# 3Phase_Driver_STUDY.net
KiCad netlist of a schematic drawn in Altium Designer
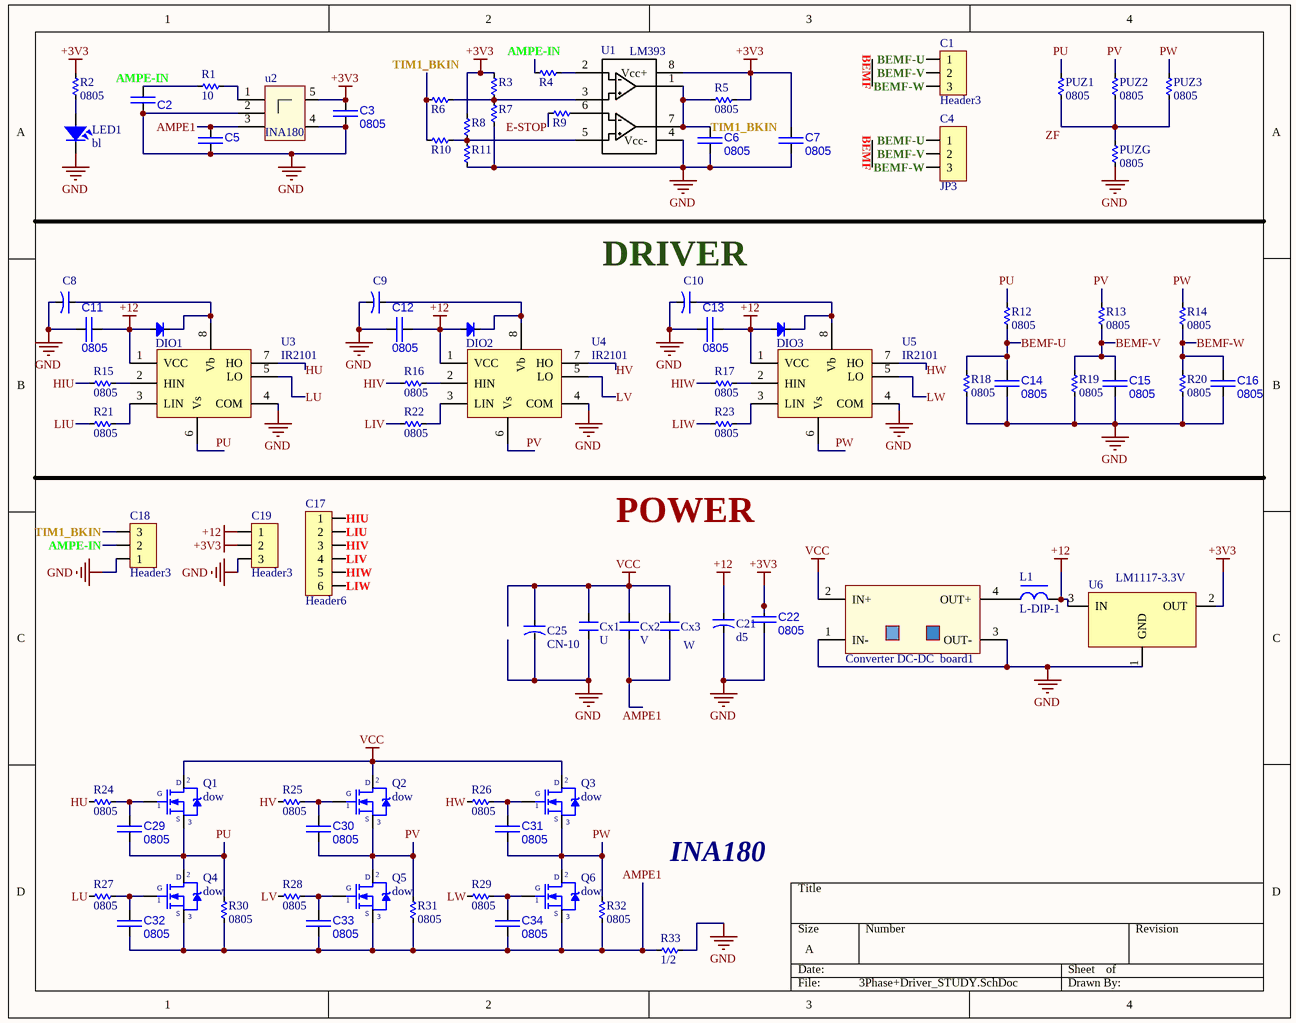
[diagram p0: 3Phase+Driver_STUDY.SchDoc]

(export (version "E")
  (design (tool "Eeschema 10.0.6"))
  (components
    (comp (ref "board1")
      (value "Converter DC-DC")
      (footprint "mini360")
      (description "Step DC-DC")
      (libsource (lib "DT2AM") (part "Converter DC-DC"))
    )
    (comp (ref "C1")
      (value "Header3")
      (footprint "Header3")
      (description "Header IDC, 3 x 1 Pin Vertical 2.54mm Pitch (Non-Boxed, Male)")
      (fields
        (field (name "MANUFACTURER") "Würth Elektronik eiSos GmbH")
        (field (name "PARTNO") "613002143121")
        (field (name "CREATED BY") "Karrer Zheng")
      )
      (libsource (lib "LIBRARY") (part "Header3"))
    )
    (comp (ref "C2")
      (value "approved sub OK")
      (footprint "CAPC2012X135N")
      (description "Capacitor SMD Cer 1.8nF 10% 50V X7R 0805")
      (fields (field (name "TOLERANCE") "±10%"))
      (libsource (lib "My library altium") (part "CAP C_0805"))
    )
    (comp (ref "C3")
      (value "0805")
      (footprint "CAPC2012X135N")
      (description "Capacitor SMD Cer 1.8nF 10% 50V X7R 0805")
      (fields (field (name "TOLERANCE") "±10%") (field (name "Comment") "approved sub OK"))
      (libsource (lib "My library altium") (part "CAP C_0805"))
    )
    (comp (ref "C4")
      (value "JP3")
      (footprint "JP3-C1T")
      (description "WR-PHD 2.54 mm Angled Socket Header")
      (fields
        (field (name "MANUFACTURER") "Würth Elektronik eiSos GmbH")
        (field (name "PARTNO") "613003143121")
        (field (name "CREATED BY") "Karrer Zheng")
      )
      (libsource (lib "LIBRARY") (part "JP3"))
    )
    (comp (ref "C5")
      (value "approved sub OK")
      (footprint "CAPC2012X135N")
      (description "Capacitor SMD Cer 1.8nF 10% 50V X7R 0805")
      (fields (field (name "TOLERANCE") "±10%"))
      (libsource (lib "My library altium") (part "CAP C_0805"))
    )
    (comp (ref "C6")
      (value "0805")
      (footprint "CAPC2012X135N")
      (description "Capacitor SMD Cer 1.8nF 10% 50V X7R 0805")
      (fields (field (name "TOLERANCE") "±10%") (field (name "Comment") "approved sub OK"))
      (libsource (lib "My library altium") (part "CAP C_0805"))
    )
    (comp (ref "C7")
      (value "0805")
      (footprint "CAPC2012X135N")
      (description "Capacitor SMD Cer 1.8nF 10% 50V X7R 0805")
      (fields (field (name "TOLERANCE") "±10%") (field (name "Comment") "approved sub OK"))
      (libsource (lib "My library altium") (part "CAP C_0805"))
    )
    (comp (ref "C8")
      (value "CN-ALU-SMD")
      (footprint "CAP-ALU-SMD-5.5x5.5")
      (description "Polarized Capacitor (Axial)")
      (fields (field (name "PUBLISHER") "Altium Limited"))
      (libsource (lib "LIBRARY") (part "CN-ALU-SMD"))
    )
    (comp (ref "C9")
      (value "CN-ALU-SMD")
      (footprint "CAP-ALU-SMD-5.5x5.5")
      (description "Polarized Capacitor (Axial)")
      (fields (field (name "PUBLISHER") "Altium Limited"))
      (libsource (lib "LIBRARY") (part "CN-ALU-SMD"))
    )
    (comp (ref "C10")
      (value "CN-ALU-SMD")
      (footprint "CAP-ALU-SMD-5.5x5.5")
      (description "Polarized Capacitor (Axial)")
      (fields (field (name "PUBLISHER") "Altium Limited"))
      (libsource (lib "LIBRARY") (part "CN-ALU-SMD"))
    )
    (comp (ref "C11")
      (value "0805")
      (footprint "CAPC2012X135N")
      (description "Capacitor SMD Cer 1.8nF 10% 50V X7R 0805")
      (fields (field (name "TOLERANCE") "±10%") (field (name "Comment") "approved sub OK"))
      (libsource (lib "My library altium") (part "CAP C_0805"))
    )
    (comp (ref "C12")
      (value "0805")
      (footprint "CAPC2012X135N")
      (description "Capacitor SMD Cer 1.8nF 10% 50V X7R 0805")
      (fields (field (name "TOLERANCE") "±10%") (field (name "Comment") "approved sub OK"))
      (libsource (lib "My library altium") (part "CAP C_0805"))
    )
    (comp (ref "C13")
      (value "0805")
      (footprint "CAPC2012X135N")
      (description "Capacitor SMD Cer 1.8nF 10% 50V X7R 0805")
      (fields (field (name "TOLERANCE") "±10%") (field (name "Comment") "approved sub OK"))
      (libsource (lib "My library altium") (part "CAP C_0805"))
    )
    (comp (ref "C14")
      (value "0805")
      (footprint "CAPC2012X135N")
      (description "Capacitor SMD Cer 1.8nF 10% 50V X7R 0805")
      (fields (field (name "TOLERANCE") "±10%") (field (name "Comment") "approved sub OK"))
      (libsource (lib "My library altium") (part "CAP C_0805"))
    )
    (comp (ref "C15")
      (value "0805")
      (footprint "CAPC2012X135N")
      (description "Capacitor SMD Cer 1.8nF 10% 50V X7R 0805")
      (fields (field (name "TOLERANCE") "±10%") (field (name "Comment") "approved sub OK"))
      (libsource (lib "My library altium") (part "CAP C_0805"))
    )
    (comp (ref "C16")
      (value "0805")
      (footprint "CAPC2012X135N")
      (description "Capacitor SMD Cer 1.8nF 10% 50V X7R 0805")
      (fields (field (name "TOLERANCE") "±10%") (field (name "Comment") "approved sub OK"))
      (libsource (lib "My library altium") (part "CAP C_0805"))
    )
    (comp (ref "C17")
      (value "Header6")
      (footprint "Header6")
      (description "Header IDC, 6 x 1 Pin Vertical 2.54mm Pitch (Non-Boxed, Male)")
      (fields
        (field (name "MANUFACTURER") "Würth Elektronik eiSos GmbH")
        (field (name "PARTNO") "613002143121")
        (field (name "CREATED BY") "Karrer Zheng")
      )
      (libsource (lib "LIBRARY") (part "Header6"))
    )
    (comp (ref "C18")
      (value "Header3")
      (footprint "Header3")
      (description "Header IDC, 3 x 1 Pin Vertical 2.54mm Pitch (Non-Boxed, Male)")
      (fields
        (field (name "MANUFACTURER") "Würth Elektronik eiSos GmbH")
        (field (name "PARTNO") "613002143121")
        (field (name "CREATED BY") "Karrer Zheng")
      )
      (libsource (lib "") (part "Header3_1"))
    )
    (comp (ref "C19")
      (value "Header3")
      (footprint "Header3")
      (description "Header IDC, 3 x 1 Pin Vertical 2.54mm Pitch (Non-Boxed, Male)")
      (fields
        (field (name "MANUFACTURER") "Würth Elektronik eiSos GmbH")
        (field (name "PARTNO") "613002143121")
        (field (name "CREATED BY") "Karrer Zheng")
      )
      (libsource (lib "LIBRARY") (part "Header3"))
    )
    (comp (ref "C21")
      (value "d5")
      (footprint "CA-ALU-5")
      (description "Capacitor (Semiconductor SIM Model)")
      (fields (field (name "PUBLISHER") "Altium Limited"))
      (libsource (lib "LIBRARY") (part "CN-ALU-DIP"))
    )
    (comp (ref "C22")
      (value "0805")
      (footprint "CAPC2012X135N")
      (description "Capacitor SMD Cer 1.8nF 10% 50V X7R 0805")
      (fields (field (name "TOLERANCE") "±10%") (field (name "Comment") "approved sub OK"))
      (libsource (lib "My library altium") (part "CAP C_0805"))
    )
    (comp (ref "C25")
      (value "CN-10")
      (footprint "CA-ALU-10")
      (description "Capacitor (Semiconductor SIM Model)")
      (fields (field (name "PUBLISHER") "Altium Limited"))
      (libsource (lib "LIBRARY") (part "CN-ALU-DIP"))
    )
    (comp (ref "C29")
      (value "0805")
      (footprint "CAPC2012X135N")
      (description "Capacitor SMD Cer 1.8nF 10% 50V X7R 0805")
      (fields (field (name "TOLERANCE") "±10%") (field (name "Comment") "approved sub OK"))
      (libsource (lib "My library altium") (part "CAP C_0805"))
    )
    (comp (ref "C30")
      (value "0805")
      (footprint "CAPC2012X135N")
      (description "Capacitor SMD Cer 1.8nF 10% 50V X7R 0805")
      (fields (field (name "TOLERANCE") "±10%") (field (name "Comment") "approved sub OK"))
      (libsource (lib "My library altium") (part "CAP C_0805"))
    )
    (comp (ref "C31")
      (value "0805")
      (footprint "CAPC2012X135N")
      (description "Capacitor SMD Cer 1.8nF 10% 50V X7R 0805")
      (fields (field (name "TOLERANCE") "±10%") (field (name "Comment") "approved sub OK"))
      (libsource (lib "My library altium") (part "CAP C_0805"))
    )
    (comp (ref "C32")
      (value "0805")
      (footprint "CAPC2012X135N")
      (description "Capacitor SMD Cer 1.8nF 10% 50V X7R 0805")
      (fields (field (name "TOLERANCE") "±10%") (field (name "Comment") "approved sub OK"))
      (libsource (lib "My library altium") (part "CAP C_0805"))
    )
    (comp (ref "C33")
      (value "0805")
      (footprint "CAPC2012X135N")
      (description "Capacitor SMD Cer 1.8nF 10% 50V X7R 0805")
      (fields (field (name "TOLERANCE") "±10%") (field (name "Comment") "approved sub OK"))
      (libsource (lib "My library altium") (part "CAP C_0805"))
    )
    (comp (ref "C34")
      (value "0805")
      (footprint "CAPC2012X135N")
      (description "Capacitor SMD Cer 1.8nF 10% 50V X7R 0805")
      (fields (field (name "TOLERANCE") "±10%") (field (name "Comment") "approved sub OK"))
      (libsource (lib "My library altium") (part "CAP C_0805"))
    )
    (comp (ref "Cx1") (value "U") (footprint "CN2-LT") (libsource (lib "LIBRARY") (part "CN")))
    (comp (ref "Cx2") (value "V") (footprint "CN2-LT") (libsource (lib "LIBRARY") (part "CN")))
    (comp (ref "Cx3") (value "W") (footprint "CN2-LT") (libsource (lib "LIBRARY") (part "CN")))
    (comp (ref "DIO1")
      (value "Diode SMD")
      (footprint "DIO-SMD-123")
      (description "Default Diode")
      (fields (field (name "PUBLISHER") "Altium Limited"))
      (libsource (lib "LIBRARY") (part "Diode SMD"))
    )
    (comp (ref "DIO2")
      (value "Diode SMD")
      (footprint "DIO-SMD-123")
      (description "Default Diode")
      (fields (field (name "PUBLISHER") "Altium Limited"))
      (libsource (lib "LIBRARY") (part "Diode SMD"))
    )
    (comp (ref "DIO3")
      (value "Diode SMD")
      (footprint "DIO-SMD-123")
      (description "Default Diode")
      (fields (field (name "PUBLISHER") "Altium Limited"))
      (libsource (lib "LIBRARY") (part "Diode SMD"))
    )
    (comp (ref "L1")
      (value "L-DIP-1")
      (footprint "L-DIP-M-5.3")
      (description "Inductor")
      (libsource (lib "LIBRARY") (part "L-DIP-1"))
    )
    (comp (ref "LED1") (value "bl") (footprint "LED-0805-Blue") (libsource (lib "LIBRARY") (part "LED SMD")))
    (comp (ref "PUZ1")
      (value "0805")
      (footprint "RES-SMD-0805")
      (description "Resistor")
      (fields
        (field (name "MANUFACTURER") "Generic Components")
        (field (name "PUBLISHER") "Altium Hobart Technology Centre")
      )
      (libsource (lib "LIBRARY") (part "Res-SMD"))
    )
    (comp (ref "PUZ2")
      (value "0805")
      (footprint "RES-SMD-0805")
      (description "Resistor")
      (fields
        (field (name "MANUFACTURER") "Generic Components")
        (field (name "PUBLISHER") "Altium Hobart Technology Centre")
      )
      (libsource (lib "LIBRARY") (part "Res-SMD"))
    )
    (comp (ref "PUZ3")
      (value "0805")
      (footprint "RES-SMD-0805")
      (description "Resistor")
      (fields
        (field (name "MANUFACTURER") "Generic Components")
        (field (name "PUBLISHER") "Altium Hobart Technology Centre")
      )
      (libsource (lib "LIBRARY") (part "Res-SMD"))
    )
    (comp (ref "PUZG")
      (value "0805")
      (footprint "RES-SMD-0805")
      (description "Resistor")
      (fields
        (field (name "MANUFACTURER") "Generic Components")
        (field (name "PUBLISHER") "Altium Hobart Technology Centre")
      )
      (libsource (lib "LIBRARY") (part "Res-SMD"))
    )
    (comp (ref "Q1")
      (value "dow")
      (footprint "TO220NH")
      (description "MOSFET N - CHANNEL 500V - 0.75 - 8A - TO-220")
      (libsource (lib "LIBRARY") (part "IRF840"))
    )
    (comp (ref "Q2")
      (value "dow")
      (footprint "TO220NH")
      (description "MOSFET N - CHANNEL 500V - 0.75 - 8A - TO-220")
      (libsource (lib "LIBRARY") (part "IRF840"))
    )
    (comp (ref "Q3")
      (value "dow")
      (footprint "TO220NH")
      (description "MOSFET N - CHANNEL 500V - 0.75 - 8A - TO-220")
      (libsource (lib "LIBRARY") (part "IRF840"))
    )
    (comp (ref "Q4")
      (value "dow")
      (footprint "TO220NH")
      (description "MOSFET N - CHANNEL 500V - 0.75 - 8A - TO-220")
      (libsource (lib "LIBRARY") (part "IRF840"))
    )
    (comp (ref "Q5")
      (value "dow")
      (footprint "TO220NH")
      (description "MOSFET N - CHANNEL 500V - 0.75 - 8A - TO-220")
      (libsource (lib "LIBRARY") (part "IRF840"))
    )
    (comp (ref "Q6")
      (value "dow")
      (footprint "TO220NH")
      (description "MOSFET N - CHANNEL 500V - 0.75 - 8A - TO-220")
      (libsource (lib "LIBRARY") (part "IRF840"))
    )
    (comp (ref "R1")
      (value "10")
      (footprint "RES-SMD-0805")
      (description "Resistor")
      (fields
        (field (name "MANUFACTURER") "Generic Components")
        (field (name "PUBLISHER") "Altium Hobart Technology Centre")
      )
      (libsource (lib "LIBRARY") (part "Res-SMD"))
    )
    (comp (ref "R2")
      (value "0805")
      (footprint "RES-SMD-0805")
      (description "Resistor")
      (fields
        (field (name "MANUFACTURER") "Generic Components")
        (field (name "PUBLISHER") "Altium Hobart Technology Centre")
      )
      (libsource (lib "LIBRARY") (part "Res-SMD"))
    )
    (comp (ref "R3")
      (value "0805")
      (footprint "RES-SMD-0805")
      (description "Resistor")
      (fields
        (field (name "MANUFACTURER") "Generic Components")
        (field (name "PUBLISHER") "Altium Hobart Technology Centre")
      )
      (libsource (lib "LIBRARY") (part "Res-SMD"))
    )
    (comp (ref "R4")
      (value "0805")
      (footprint "RES-SMD-0805")
      (description "Resistor")
      (fields
        (field (name "MANUFACTURER") "Generic Components")
        (field (name "PUBLISHER") "Altium Hobart Technology Centre")
      )
      (libsource (lib "LIBRARY") (part "Res-SMD"))
    )
    (comp (ref "R5")
      (value "0805")
      (footprint "RES-SMD-0805")
      (description "Resistor")
      (fields
        (field (name "MANUFACTURER") "Generic Components")
        (field (name "PUBLISHER") "Altium Hobart Technology Centre")
      )
      (libsource (lib "LIBRARY") (part "Res-SMD"))
    )
    (comp (ref "R6")
      (value "0805")
      (footprint "RES-SMD-0805")
      (description "Resistor")
      (fields
        (field (name "MANUFACTURER") "Generic Components")
        (field (name "PUBLISHER") "Altium Hobart Technology Centre")
      )
      (libsource (lib "LIBRARY") (part "Res-SMD"))
    )
    (comp (ref "R7")
      (value "0805")
      (footprint "RES-SMD-0805")
      (description "Resistor")
      (fields
        (field (name "MANUFACTURER") "Generic Components")
        (field (name "PUBLISHER") "Altium Hobart Technology Centre")
      )
      (libsource (lib "LIBRARY") (part "Res-SMD"))
    )
    (comp (ref "R8")
      (value "0805")
      (footprint "RES-SMD-0805")
      (description "Resistor")
      (fields
        (field (name "MANUFACTURER") "Generic Components")
        (field (name "PUBLISHER") "Altium Hobart Technology Centre")
      )
      (libsource (lib "LIBRARY") (part "Res-SMD"))
    )
    (comp (ref "R9")
      (value "0805")
      (footprint "RES-SMD-0805")
      (description "Resistor")
      (fields
        (field (name "MANUFACTURER") "Generic Components")
        (field (name "PUBLISHER") "Altium Hobart Technology Centre")
      )
      (libsource (lib "LIBRARY") (part "Res-SMD"))
    )
    (comp (ref "R10")
      (value "0805")
      (footprint "RES-SMD-0805")
      (description "Resistor")
      (fields
        (field (name "MANUFACTURER") "Generic Components")
        (field (name "PUBLISHER") "Altium Hobart Technology Centre")
      )
      (libsource (lib "LIBRARY") (part "Res-SMD"))
    )
    (comp (ref "R11")
      (value "0805")
      (footprint "RES-SMD-0805")
      (description "Resistor")
      (fields
        (field (name "MANUFACTURER") "Generic Components")
        (field (name "PUBLISHER") "Altium Hobart Technology Centre")
      )
      (libsource (lib "LIBRARY") (part "Res-SMD"))
    )
    (comp (ref "R12")
      (value "0805")
      (footprint "RES-SMD-0805")
      (description "Resistor")
      (fields
        (field (name "MANUFACTURER") "Generic Components")
        (field (name "PUBLISHER") "Altium Hobart Technology Centre")
      )
      (libsource (lib "LIBRARY") (part "Res-SMD"))
    )
    (comp (ref "R13")
      (value "0805")
      (footprint "RES-SMD-0805")
      (description "Resistor")
      (fields
        (field (name "MANUFACTURER") "Generic Components")
        (field (name "PUBLISHER") "Altium Hobart Technology Centre")
      )
      (libsource (lib "LIBRARY") (part "Res-SMD"))
    )
    (comp (ref "R14")
      (value "0805")
      (footprint "RES-SMD-0805")
      (description "Resistor")
      (fields
        (field (name "MANUFACTURER") "Generic Components")
        (field (name "PUBLISHER") "Altium Hobart Technology Centre")
      )
      (libsource (lib "LIBRARY") (part "Res-SMD"))
    )
    (comp (ref "R15")
      (value "0805")
      (footprint "RES-SMD-0805")
      (description "Resistor")
      (fields
        (field (name "MANUFACTURER") "Generic Components")
        (field (name "PUBLISHER") "Altium Hobart Technology Centre")
      )
      (libsource (lib "LIBRARY") (part "Res-SMD"))
    )
    (comp (ref "R16")
      (value "0805")
      (footprint "RES-SMD-0805")
      (description "Resistor")
      (fields
        (field (name "MANUFACTURER") "Generic Components")
        (field (name "PUBLISHER") "Altium Hobart Technology Centre")
      )
      (libsource (lib "LIBRARY") (part "Res-SMD"))
    )
    (comp (ref "R17")
      (value "0805")
      (footprint "RES-SMD-0805")
      (description "Resistor")
      (fields
        (field (name "MANUFACTURER") "Generic Components")
        (field (name "PUBLISHER") "Altium Hobart Technology Centre")
      )
      (libsource (lib "LIBRARY") (part "Res-SMD"))
    )
    (comp (ref "R18")
      (value "0805")
      (footprint "RES-SMD-0805")
      (description "Resistor")
      (fields
        (field (name "MANUFACTURER") "Generic Components")
        (field (name "PUBLISHER") "Altium Hobart Technology Centre")
      )
      (libsource (lib "LIBRARY") (part "Res-SMD"))
    )
    (comp (ref "R19")
      (value "0805")
      (footprint "RES-SMD-0805")
      (description "Resistor")
      (fields
        (field (name "MANUFACTURER") "Generic Components")
        (field (name "PUBLISHER") "Altium Hobart Technology Centre")
      )
      (libsource (lib "LIBRARY") (part "Res-SMD"))
    )
    (comp (ref "R20")
      (value "0805")
      (footprint "RES-SMD-0805")
      (description "Resistor")
      (fields
        (field (name "MANUFACTURER") "Generic Components")
        (field (name "PUBLISHER") "Altium Hobart Technology Centre")
      )
      (libsource (lib "LIBRARY") (part "Res-SMD"))
    )
    (comp (ref "R21")
      (value "0805")
      (footprint "RES-SMD-0805")
      (description "Resistor")
      (fields
        (field (name "MANUFACTURER") "Generic Components")
        (field (name "PUBLISHER") "Altium Hobart Technology Centre")
      )
      (libsource (lib "LIBRARY") (part "Res-SMD"))
    )
    (comp (ref "R22")
      (value "0805")
      (footprint "RES-SMD-0805")
      (description "Resistor")
      (fields
        (field (name "MANUFACTURER") "Generic Components")
        (field (name "PUBLISHER") "Altium Hobart Technology Centre")
      )
      (libsource (lib "LIBRARY") (part "Res-SMD"))
    )
    (comp (ref "R23")
      (value "0805")
      (footprint "RES-SMD-0805")
      (description "Resistor")
      (fields
        (field (name "MANUFACTURER") "Generic Components")
        (field (name "PUBLISHER") "Altium Hobart Technology Centre")
      )
      (libsource (lib "LIBRARY") (part "Res-SMD"))
    )
    (comp (ref "R24")
      (value "0805")
      (footprint "RES-SMD-0805")
      (description "Resistor")
      (fields
        (field (name "MANUFACTURER") "Generic Components")
        (field (name "PUBLISHER") "Altium Hobart Technology Centre")
      )
      (libsource (lib "LIBRARY") (part "Res-SMD"))
    )
    (comp (ref "R25")
      (value "0805")
      (footprint "RES-SMD-0805")
      (description "Resistor")
      (fields
        (field (name "MANUFACTURER") "Generic Components")
        (field (name "PUBLISHER") "Altium Hobart Technology Centre")
      )
      (libsource (lib "LIBRARY") (part "Res-SMD"))
    )
    (comp (ref "R26")
      (value "0805")
      (footprint "RES-SMD-0805")
      (description "Resistor")
      (fields
        (field (name "MANUFACTURER") "Generic Components")
        (field (name "PUBLISHER") "Altium Hobart Technology Centre")
      )
      (libsource (lib "LIBRARY") (part "Res-SMD"))
    )
    (comp (ref "R27")
      (value "0805")
      (footprint "RES-SMD-0805")
      (description "Resistor")
      (fields
        (field (name "MANUFACTURER") "Generic Components")
        (field (name "PUBLISHER") "Altium Hobart Technology Centre")
      )
      (libsource (lib "LIBRARY") (part "Res-SMD"))
    )
    (comp (ref "R28")
      (value "0805")
      (footprint "RES-SMD-0805")
      (description "Resistor")
      (fields
        (field (name "MANUFACTURER") "Generic Components")
        (field (name "PUBLISHER") "Altium Hobart Technology Centre")
      )
      (libsource (lib "LIBRARY") (part "Res-SMD"))
    )
    (comp (ref "R29")
      (value "0805")
      (footprint "RES-SMD-0805")
      (description "Resistor")
      (fields
        (field (name "MANUFACTURER") "Generic Components")
        (field (name "PUBLISHER") "Altium Hobart Technology Centre")
      )
      (libsource (lib "LIBRARY") (part "Res-SMD"))
    )
    (comp (ref "R30")
      (value "0805")
      (footprint "RES-SMD-0805")
      (description "Resistor")
      (fields
        (field (name "MANUFACTURER") "Generic Components")
        (field (name "PUBLISHER") "Altium Hobart Technology Centre")
      )
      (libsource (lib "LIBRARY") (part "Res-SMD"))
    )
    (comp (ref "R31")
      (value "0805")
      (footprint "RES-SMD-0805")
      (description "Resistor")
      (fields
        (field (name "MANUFACTURER") "Generic Components")
        (field (name "PUBLISHER") "Altium Hobart Technology Centre")
      )
      (libsource (lib "LIBRARY") (part "Res-SMD"))
    )
    (comp (ref "R32")
      (value "0805")
      (footprint "RES-SMD-0805")
      (description "Resistor")
      (fields
        (field (name "MANUFACTURER") "Generic Components")
        (field (name "PUBLISHER") "Altium Hobart Technology Centre")
      )
      (libsource (lib "LIBRARY") (part "Res-SMD"))
    )
    (comp (ref "R33")
      (value "1/2")
      (footprint "RES-1/2W")
      (description "Res")
      (fields
        (field (name "MANUFACTURER") "Generic Components")
        (field (name "PUBLISHER") "Altium Hobart Technology Centre")
      )
      (libsource (lib "LIBRARY") (part "Res"))
    )
    (comp (ref "U1")
      (value "LM393")
      (footprint "SO8")
      (description "IC DUAL COMPARATOR")
      (libsource (lib "LIBRARY") (part "LM393"))
    )
    (comp (ref "u2")
      (value "INA180")
      (footprint "SOT-23-5")
      (description "SMD_IC_SOT-23-5")
      (libsource (lib "DT2AM") (part "SOT-23-5_SMD"))
    )
    (comp (ref "U3")
      (value "IR2101")
      (footprint "SO8")
      (description "Half-Bridge Driver")
      (libsource (lib "LIBRARY") (part "IR2101S"))
    )
    (comp (ref "U4")
      (value "IR2101")
      (footprint "SO8")
      (description "Half-Bridge Driver")
      (libsource (lib "LIBRARY") (part "IR2101S"))
    )
    (comp (ref "U5")
      (value "IR2101")
      (footprint "SO8")
      (description "Half-Bridge Driver")
      (libsource (lib "LIBRARY") (part "IR2101S"))
    )
    (comp (ref "U6")
      (value "LM1117-3.3V")
      (footprint "SOT223")
      (description "800mA Low-Dropout Linear Regulator")
      (fields (field (name "CREATOR") "Nguyen Ba Bien"))
      (libsource (lib "LIBRARY") (part "LM1117"))
    )
  )
  (nets
    (net (code "1") (name "+3V3") (class "Default")
      (node (ref "C19") (pin "2") (pinfunction "2_2") (pintype "passive"))
      (node (ref "C22") (pin "2") (pintype "passive"))
      (node (ref "C3") (pin "2") (pintype "passive"))
      (node (ref "C7") (pin "2") (pintype "passive"))
      (node (ref "R2") (pin "1") (pinfunction "1_1") (pintype "passive"))
      (node (ref "R3") (pin "2") (pinfunction "2_2") (pintype "passive"))
      (node (ref "R5") (pin "2") (pinfunction "2_2") (pintype "passive"))
      (node (ref "R8") (pin "2") (pinfunction "2_2") (pintype "passive"))
      (node (ref "U1") (pin "8") (pinfunction "Vcc+_8") (pintype "passive"))
      (node (ref "U6") (pin "2") (pinfunction "OUT_2") (pintype "passive"))
      (node (ref "u2") (pin "5") (pinfunction "OUT_5") (pintype "passive"))
    )
    (net (code "2") (name "+12") (class "Default")
      (node (ref "C11") (pin "2") (pintype "passive"))
      (node (ref "C12") (pin "2") (pintype "passive"))
      (node (ref "C13") (pin "2") (pintype "passive"))
      (node (ref "C19") (pin "1") (pinfunction "1_1") (pintype "passive"))
      (node (ref "C21") (pin "1") (pinfunction "1_1") (pintype "passive"))
      (node (ref "DIO1") (pin "1") (pinfunction "A_1") (pintype "passive"))
      (node (ref "DIO2") (pin "1") (pinfunction "A_1") (pintype "passive"))
      (node (ref "DIO3") (pin "1") (pinfunction "A_1") (pintype "passive"))
      (node (ref "L1") (pin "2") (pinfunction "2_2") (pintype "passive"))
      (node (ref "U3") (pin "1") (pinfunction "VCC_1") (pintype "passive"))
      (node (ref "U4") (pin "1") (pinfunction "VCC_1") (pintype "passive"))
      (node (ref "U5") (pin "1") (pinfunction "VCC_1") (pintype "passive"))
      (node (ref "U6") (pin "3") (pinfunction "IN_3") (pintype "passive"))
    )
    (net (code "3") (name "/AMPE-IN") (class "Default")
      (node (ref "C18") (pin "2") (pinfunction "2_2") (pintype "passive"))
      (node (ref "C2") (pin "1") (pintype "passive"))
      (node (ref "R1") (pin "2") (pinfunction "2_2") (pintype "passive"))
      (node (ref "R4") (pin "2") (pinfunction "2_2") (pintype "passive"))
    )
    (net (code "4") (name "/AMPE1") (class "Default")
      (node (ref "C32") (pin "2") (pintype "passive"))
      (node (ref "C33") (pin "2") (pintype "passive"))
      (node (ref "C34") (pin "2") (pintype "passive"))
      (node (ref "C5") (pin "2") (pintype "passive"))
      (node (ref "Cx2") (pin "1") (pinfunction "1_1") (pintype "passive"))
      (node (ref "Cx3") (pin "1") (pinfunction "1_1") (pintype "passive"))
      (node (ref "Q4") (pin "3") (pinfunction "S_3") (pintype "passive"))
      (node (ref "Q5") (pin "3") (pinfunction "S_3") (pintype "passive"))
      (node (ref "Q6") (pin "3") (pinfunction "S_3") (pintype "passive"))
      (node (ref "R30") (pin "2") (pinfunction "2_2") (pintype "passive"))
      (node (ref "R31") (pin "2") (pinfunction "2_2") (pintype "passive"))
      (node (ref "R32") (pin "2") (pinfunction "2_2") (pintype "passive"))
      (node (ref "R33") (pin "2") (pinfunction "2_2") (pintype "passive"))
      (node (ref "u2") (pin "3") (pinfunction "OUT_3") (pintype "passive"))
    )
    (net (code "5") (name "/BEMF-U") (class "Default")
      (node (ref "C1") (pin "1") (pinfunction "1_1") (pintype "passive"))
      (node (ref "C14") (pin "1") (pintype "passive"))
      (node (ref "C4") (pin "1") (pinfunction "1_1") (pintype "passive"))
      (node (ref "R12") (pin "2") (pinfunction "2_2") (pintype "passive"))
      (node (ref "R18") (pin "1") (pinfunction "1_1") (pintype "passive"))
    )
    (net (code "6") (name "/BEMF-V") (class "Default")
      (node (ref "C1") (pin "2") (pinfunction "2_2") (pintype "passive"))
      (node (ref "C15") (pin "1") (pintype "passive"))
      (node (ref "C4") (pin "2") (pinfunction "2_2") (pintype "passive"))
      (node (ref "R13") (pin "2") (pinfunction "2_2") (pintype "passive"))
      (node (ref "R19") (pin "1") (pinfunction "1_1") (pintype "passive"))
    )
    (net (code "7") (name "/BEMF-W") (class "Default")
      (node (ref "C1") (pin "3") (pinfunction "3_3") (pintype "passive"))
      (node (ref "C16") (pin "1") (pintype "passive"))
      (node (ref "C4") (pin "3") (pinfunction "3_3") (pintype "passive"))
      (node (ref "R14") (pin "2") (pinfunction "2_2") (pintype "passive"))
      (node (ref "R20") (pin "1") (pinfunction "1_1") (pintype "passive"))
    )
    (net (code "8") (name "/E-STOP") (class "Default")
      (node (ref "R9") (pin "2") (pinfunction "2_2") (pintype "passive"))
    )
    (net (code "9") (name "/HIU") (class "Default")
      (node (ref "C17") (pin "1") (pinfunction "1_1") (pintype "passive"))
      (node (ref "R15") (pin "2") (pinfunction "2_2") (pintype "passive"))
    )
    (net (code "10") (name "/HIV") (class "Default")
      (node (ref "C17") (pin "3") (pinfunction "3_3") (pintype "passive"))
      (node (ref "R16") (pin "2") (pinfunction "2_2") (pintype "passive"))
    )
    (net (code "11") (name "/HIW") (class "Default")
      (node (ref "C17") (pin "5") (pinfunction "5_5") (pintype "passive"))
      (node (ref "R17") (pin "2") (pinfunction "2_2") (pintype "passive"))
    )
    (net (code "12") (name "/HU") (class "Default")
      (node (ref "R24") (pin "2") (pinfunction "2_2") (pintype "passive"))
      (node (ref "U3") (pin "7") (pinfunction "HO_7") (pintype "passive"))
    )
    (net (code "13") (name "/HV") (class "Default")
      (node (ref "R25") (pin "2") (pinfunction "2_2") (pintype "passive"))
      (node (ref "U4") (pin "7") (pinfunction "HO_7") (pintype "passive"))
    )
    (net (code "14") (name "/HW") (class "Default")
      (node (ref "R26") (pin "2") (pinfunction "2_2") (pintype "passive"))
      (node (ref "U5") (pin "7") (pinfunction "HO_7") (pintype "passive"))
    )
    (net (code "15") (name "/LIU") (class "Default")
      (node (ref "C17") (pin "2") (pinfunction "2_2") (pintype "passive"))
      (node (ref "R21") (pin "2") (pinfunction "2_2") (pintype "passive"))
    )
    (net (code "16") (name "/LIV") (class "Default")
      (node (ref "C17") (pin "4") (pinfunction "4_4") (pintype "passive"))
      (node (ref "R22") (pin "2") (pinfunction "2_2") (pintype "passive"))
    )
    (net (code "17") (name "/LIW") (class "Default")
      (node (ref "C17") (pin "6") (pinfunction "6_6") (pintype "passive"))
      (node (ref "R23") (pin "2") (pinfunction "2_2") (pintype "passive"))
    )
    (net (code "18") (name "/LU") (class "Default")
      (node (ref "R27") (pin "2") (pinfunction "2_2") (pintype "passive"))
      (node (ref "U3") (pin "5") (pinfunction "LO_5") (pintype "passive"))
    )
    (net (code "19") (name "/LV") (class "Default")
      (node (ref "R28") (pin "2") (pinfunction "2_2") (pintype "passive"))
      (node (ref "U4") (pin "5") (pinfunction "LO_5") (pintype "passive"))
    )
    (net (code "20") (name "/LW") (class "Default")
      (node (ref "R29") (pin "2") (pinfunction "2_2") (pintype "passive"))
      (node (ref "U5") (pin "5") (pinfunction "LO_5") (pintype "passive"))
    )
    (net (code "21") (name "/PU") (class "Default")
      (node (ref "C29") (pin "2") (pintype "passive"))
      (node (ref "PUZ1") (pin "1") (pinfunction "1_1") (pintype "passive"))
      (node (ref "Q1") (pin "3") (pinfunction "S_3") (pintype "passive"))
      (node (ref "Q4") (pin "2") (pinfunction "D_2") (pintype "passive"))
      (node (ref "R12") (pin "1") (pinfunction "1_1") (pintype "passive"))
      (node (ref "R30") (pin "1") (pinfunction "1_1") (pintype "passive"))
      (node (ref "U3") (pin "6") (pinfunction "Vs_6") (pintype "passive"))
    )
    (net (code "22") (name "/PV") (class "Default")
      (node (ref "C30") (pin "2") (pintype "passive"))
      (node (ref "PUZ2") (pin "1") (pinfunction "1_1") (pintype "passive"))
      (node (ref "Q2") (pin "3") (pinfunction "S_3") (pintype "passive"))
      (node (ref "Q5") (pin "2") (pinfunction "D_2") (pintype "passive"))
      (node (ref "R13") (pin "1") (pinfunction "1_1") (pintype "passive"))
      (node (ref "R31") (pin "1") (pinfunction "1_1") (pintype "passive"))
      (node (ref "U4") (pin "6") (pinfunction "Vs_6") (pintype "passive"))
    )
    (net (code "23") (name "/PW") (class "Default")
      (node (ref "C31") (pin "2") (pintype "passive"))
      (node (ref "PUZ3") (pin "1") (pinfunction "1_1") (pintype "passive"))
      (node (ref "Q3") (pin "3") (pinfunction "S_3") (pintype "passive"))
      (node (ref "Q6") (pin "2") (pinfunction "D_2") (pintype "passive"))
      (node (ref "R14") (pin "1") (pinfunction "1_1") (pintype "passive"))
      (node (ref "R32") (pin "1") (pinfunction "1_1") (pintype "passive"))
      (node (ref "U5") (pin "6") (pinfunction "Vs_6") (pintype "passive"))
    )
    (net (code "24") (name "/TIM1_BKIN") (class "Default")
      (node (ref "C18") (pin "3") (pinfunction "3_3") (pintype "passive"))
      (node (ref "C6") (pin "2") (pintype "passive"))
      (node (ref "R10") (pin "2") (pinfunction "2_2") (pintype "passive"))
      (node (ref "R5") (pin "1") (pinfunction "1_1") (pintype "passive"))
      (node (ref "R6") (pin "2") (pinfunction "2_2") (pintype "passive"))
      (node (ref "U1") (pin "1") (pintype "passive"))
      (node (ref "U1") (pin "7") (pintype "passive"))
    )
    (net (code "25") (name "/ZF") (class "Default")
      (node (ref "PUZ1") (pin "2") (pinfunction "2_2") (pintype "passive"))
      (node (ref "PUZ2") (pin "2") (pinfunction "2_2") (pintype "passive"))
      (node (ref "PUZ3") (pin "2") (pinfunction "2_2") (pintype "passive"))
      (node (ref "PUZG") (pin "1") (pinfunction "1_1") (pintype "passive"))
    )
    (net (code "26") (name "GND") (class "Default")
      (node (ref "C10") (pin "2") (pinfunction "2_2") (pintype "passive"))
      (node (ref "C11") (pin "1") (pintype "passive"))
      (node (ref "C12") (pin "1") (pintype "passive"))
      (node (ref "C13") (pin "1") (pintype "passive"))
      (node (ref "C14") (pin "2") (pintype "passive"))
      (node (ref "C15") (pin "2") (pintype "passive"))
      (node (ref "C16") (pin "2") (pintype "passive"))
      (node (ref "C18") (pin "1") (pinfunction "1_1") (pintype "passive"))
      (node (ref "C19") (pin "3") (pinfunction "3_3") (pintype "passive"))
      (node (ref "C2") (pin "2") (pintype "passive"))
      (node (ref "C21") (pin "2") (pinfunction "2_2") (pintype "passive"))
      (node (ref "C22") (pin "1") (pintype "passive"))
      (node (ref "C25") (pin "2") (pinfunction "2_2") (pintype "passive"))
      (node (ref "C3") (pin "1") (pintype "passive"))
      (node (ref "C5") (pin "1") (pintype "passive"))
      (node (ref "C6") (pin "1") (pintype "passive"))
      (node (ref "C7") (pin "1") (pintype "passive"))
      (node (ref "C8") (pin "2") (pinfunction "2_2") (pintype "passive"))
      (node (ref "C9") (pin "2") (pinfunction "2_2") (pintype "passive"))
      (node (ref "Cx1") (pin "1") (pinfunction "1_1") (pintype "passive"))
      (node (ref "LED1") (pin "2") (pinfunction "2_2") (pintype "passive"))
      (node (ref "PUZG") (pin "2") (pinfunction "2_2") (pintype "passive"))
      (node (ref "R11") (pin "1") (pinfunction "1_1") (pintype "passive"))
      (node (ref "R18") (pin "2") (pinfunction "2_2") (pintype "passive"))
      (node (ref "R19") (pin "2") (pinfunction "2_2") (pintype "passive"))
      (node (ref "R20") (pin "2") (pinfunction "2_2") (pintype "passive"))
      (node (ref "R33") (pin "1") (pinfunction "1_1") (pintype "passive"))
      (node (ref "R7") (pin "1") (pinfunction "1_1") (pintype "passive"))
      (node (ref "U1") (pin "4") (pinfunction "Vcc-_4") (pintype "passive"))
      (node (ref "U3") (pin "4") (pinfunction "COM_4") (pintype "passive"))
      (node (ref "U4") (pin "4") (pinfunction "COM_4") (pintype "passive"))
      (node (ref "U5") (pin "4") (pinfunction "COM_4") (pintype "passive"))
      (node (ref "U6") (pin "1") (pinfunction "GND_1") (pintype "passive"))
      (node (ref "board1") (pin "1") (pinfunction "IN-_1") (pintype "passive"))
      (node (ref "board1") (pin "3") (pinfunction "OUT-_3") (pintype "passive"))
      (node (ref "u2") (pin "2") (pinfunction "OUT_2") (pintype "passive"))
      (node (ref "u2") (pin "4") (pinfunction "OUT_4") (pintype "passive"))
    )
    (net (code "27") (name "Net-(DIO1-K)") (class "Default")
      (node (ref "C8") (pin "1") (pinfunction "1_1") (pintype "passive"))
      (node (ref "DIO1") (pin "2") (pinfunction "K_2") (pintype "passive"))
      (node (ref "U3") (pin "8") (pinfunction "Vb_8") (pintype "passive"))
    )
    (net (code "28") (name "Net-(DIO2-K)") (class "Default")
      (node (ref "C9") (pin "1") (pinfunction "1_1") (pintype "passive"))
      (node (ref "DIO2") (pin "2") (pinfunction "K_2") (pintype "passive"))
      (node (ref "U4") (pin "8") (pinfunction "Vb_8") (pintype "passive"))
    )
    (net (code "29") (name "Net-(DIO3-K)") (class "Default")
      (node (ref "C10") (pin "1") (pinfunction "1_1") (pintype "passive"))
      (node (ref "DIO3") (pin "2") (pinfunction "K_2") (pintype "passive"))
      (node (ref "U5") (pin "8") (pinfunction "Vb_8") (pintype "passive"))
    )
    (net (code "30") (name "Net-(LED1-Pad1)") (class "Default")
      (node (ref "LED1") (pin "1") (pinfunction "1_1") (pintype "passive"))
      (node (ref "R2") (pin "2") (pinfunction "2_2") (pintype "passive"))
    )
    (net (code "31") (name "Net-(Q1-G)") (class "Default")
      (node (ref "C29") (pin "1") (pintype "passive"))
      (node (ref "Q1") (pin "1") (pinfunction "G_1") (pintype "passive"))
      (node (ref "R24") (pin "1") (pinfunction "1_1") (pintype "passive"))
    )
    (net (code "32") (name "Net-(Q2-G)") (class "Default")
      (node (ref "C30") (pin "1") (pintype "passive"))
      (node (ref "Q2") (pin "1") (pinfunction "G_1") (pintype "passive"))
      (node (ref "R25") (pin "1") (pinfunction "1_1") (pintype "passive"))
    )
    (net (code "33") (name "Net-(Q3-G)") (class "Default")
      (node (ref "C31") (pin "1") (pintype "passive"))
      (node (ref "Q3") (pin "1") (pinfunction "G_1") (pintype "passive"))
      (node (ref "R26") (pin "1") (pinfunction "1_1") (pintype "passive"))
    )
    (net (code "34") (name "Net-(Q4-G)") (class "Default")
      (node (ref "C32") (pin "1") (pintype "passive"))
      (node (ref "Q4") (pin "1") (pinfunction "G_1") (pintype "passive"))
      (node (ref "R27") (pin "1") (pinfunction "1_1") (pintype "passive"))
    )
    (net (code "35") (name "Net-(Q5-G)") (class "Default")
      (node (ref "C33") (pin "1") (pintype "passive"))
      (node (ref "Q5") (pin "1") (pinfunction "G_1") (pintype "passive"))
      (node (ref "R28") (pin "1") (pinfunction "1_1") (pintype "passive"))
    )
    (net (code "36") (name "Net-(Q6-G)") (class "Default")
      (node (ref "C34") (pin "1") (pintype "passive"))
      (node (ref "Q6") (pin "1") (pinfunction "G_1") (pintype "passive"))
      (node (ref "R29") (pin "1") (pinfunction "1_1") (pintype "passive"))
    )
    (net (code "37") (name "Net-(R1-Pad1)") (class "Default")
      (node (ref "R1") (pin "1") (pinfunction "1_1") (pintype "passive"))
      (node (ref "u2") (pin "1") (pinfunction "OUT_1") (pintype "passive"))
    )
    (net (code "38") (name "Net-(R3-Pad1)") (class "Default")
      (node (ref "R3") (pin "1") (pinfunction "1_1") (pintype "passive"))
      (node (ref "R6") (pin "1") (pinfunction "1_1") (pintype "passive"))
      (node (ref "R7") (pin "2") (pinfunction "2_2") (pintype "passive"))
      (node (ref "U1") (pin "3") (pintype "passive"))
    )
    (net (code "39") (name "Net-(R4-Pad1)") (class "Default")
      (node (ref "R4") (pin "1") (pinfunction "1_1") (pintype "passive"))
      (node (ref "U1") (pin "2") (pintype "passive"))
    )
    (net (code "40") (name "Net-(R9-Pad1)") (class "Default")
      (node (ref "R9") (pin "1") (pinfunction "1_1") (pintype "passive"))
      (node (ref "U1") (pin "6") (pintype "passive"))
    )
    (net (code "41") (name "Net-(R10-Pad1)") (class "Default")
      (node (ref "R10") (pin "1") (pinfunction "1_1") (pintype "passive"))
      (node (ref "R11") (pin "2") (pinfunction "2_2") (pintype "passive"))
      (node (ref "R8") (pin "1") (pinfunction "1_1") (pintype "passive"))
      (node (ref "U1") (pin "5") (pintype "passive"))
    )
    (net (code "42") (name "Net-(U3-HIN)") (class "Default")
      (node (ref "R15") (pin "1") (pinfunction "1_1") (pintype "passive"))
      (node (ref "U3") (pin "2") (pinfunction "HIN_2") (pintype "passive"))
    )
    (net (code "43") (name "Net-(U3-LIN)") (class "Default")
      (node (ref "R21") (pin "1") (pinfunction "1_1") (pintype "passive"))
      (node (ref "U3") (pin "3") (pinfunction "LIN_3") (pintype "passive"))
    )
    (net (code "44") (name "Net-(U4-HIN)") (class "Default")
      (node (ref "R16") (pin "1") (pinfunction "1_1") (pintype "passive"))
      (node (ref "U4") (pin "2") (pinfunction "HIN_2") (pintype "passive"))
    )
    (net (code "45") (name "Net-(U4-LIN)") (class "Default")
      (node (ref "R22") (pin "1") (pinfunction "1_1") (pintype "passive"))
      (node (ref "U4") (pin "3") (pinfunction "LIN_3") (pintype "passive"))
    )
    (net (code "46") (name "Net-(U5-HIN)") (class "Default")
      (node (ref "R17") (pin "1") (pinfunction "1_1") (pintype "passive"))
      (node (ref "U5") (pin "2") (pinfunction "HIN_2") (pintype "passive"))
    )
    (net (code "47") (name "Net-(U5-LIN)") (class "Default")
      (node (ref "R23") (pin "1") (pinfunction "1_1") (pintype "passive"))
      (node (ref "U5") (pin "3") (pinfunction "LIN_3") (pintype "passive"))
    )
    (net (code "48") (name "Net-(board1-OUT+)") (class "Default")
      (node (ref "L1") (pin "1") (pinfunction "1_1") (pintype "passive"))
      (node (ref "board1") (pin "4") (pinfunction "OUT+_4") (pintype "passive"))
    )
    (net (code "49") (name "VCC") (class "Default")
      (node (ref "C25") (pin "1") (pinfunction "1_1") (pintype "passive"))
      (node (ref "Cx1") (pin "2") (pinfunction "2_2") (pintype "passive"))
      (node (ref "Cx2") (pin "2") (pinfunction "2_2") (pintype "passive"))
      (node (ref "Cx3") (pin "2") (pinfunction "2_2") (pintype "passive"))
      (node (ref "Q1") (pin "2") (pinfunction "D_2") (pintype "passive"))
      (node (ref "Q2") (pin "2") (pinfunction "D_2") (pintype "passive"))
      (node (ref "Q3") (pin "2") (pinfunction "D_2") (pintype "passive"))
      (node (ref "board1") (pin "2") (pinfunction "IN+_2") (pintype "passive"))
    )
  )
)
